# 01-USER_IO.net
KiCad netlist of a schematic drawn in Altium Designer
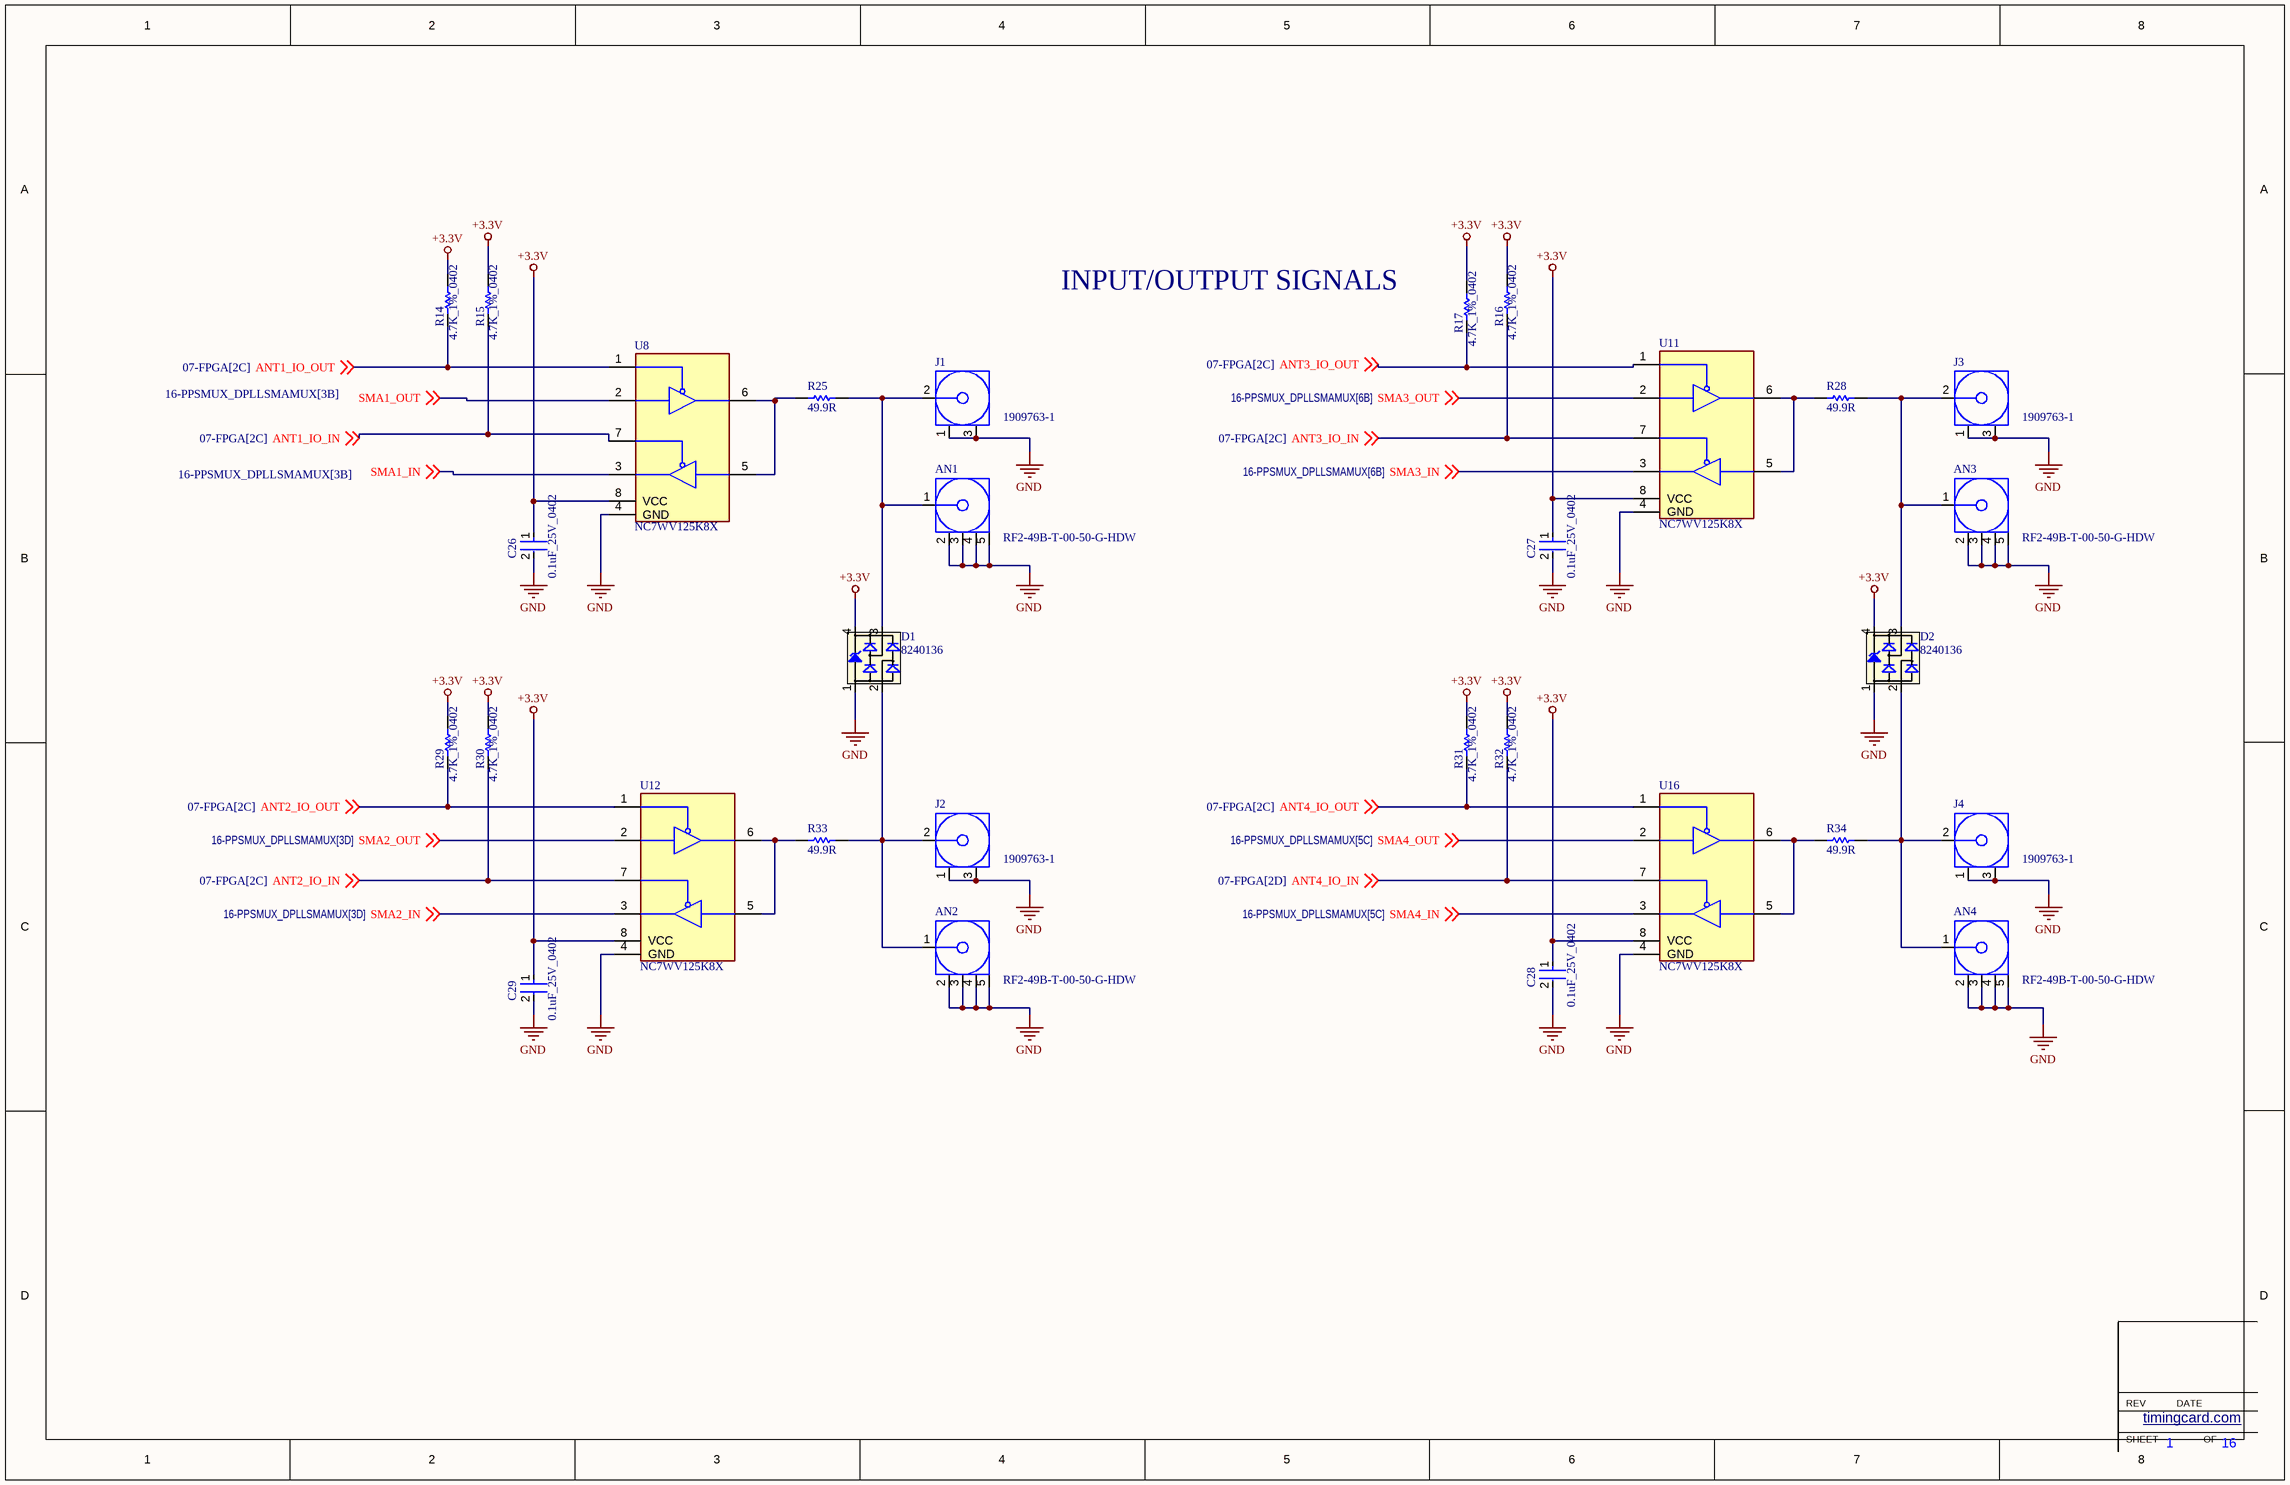
[diagram p0: 01-USER_IO.SchDoc]

(export (version "E")
  (design (tool "Eeschema 10.0.6"))
  (components
    (comp (ref "AN1")
      (value "RF2-49B-T-00-50-G-HDW")
      (footprint "AMPH-901-143-6RFX_V")
      (description "Coaxial connector, 50 Ohm, -65 to 165 degC, 5-Pin THD, RoHS, Bulk")
      (fields (field (name "MANUFACTURER") "Amphenol"))
      (libsource (lib "Altium Content Vault") (part "CN-S-4F-RF5"))
    )
    (comp (ref "AN2")
      (value "RF2-49B-T-00-50-G-HDW")
      (footprint "AMPH-901-143-6RFX_V")
      (description "Coaxial connector, 50 Ohm, -65 to 165 degC, 5-Pin THD, RoHS, Bulk")
      (fields (field (name "MANUFACTURER") "Amphenol"))
      (libsource (lib "Altium Content Vault") (part "CN-S-4F-RF5"))
    )
    (comp (ref "AN3")
      (value "RF2-49B-T-00-50-G-HDW")
      (footprint "AMPH-901-143-6RFX_V")
      (description "Coaxial connector, 50 Ohm, -65 to 165 degC, 5-Pin THD, RoHS, Bulk")
      (fields (field (name "MANUFACTURER") "Amphenol"))
      (libsource (lib "Altium Content Vault") (part "CN-S-4F-RF5"))
    )
    (comp (ref "AN4")
      (value "RF2-49B-T-00-50-G-HDW")
      (footprint "AMPH-901-143-6RFX_V")
      (description "Coaxial connector, 50 Ohm, -65 to 165 degC, 5-Pin THD, RoHS, Bulk")
      (fields (field (name "MANUFACTURER") "Amphenol"))
      (libsource (lib "Altium Content Vault") (part "CN-S-4F-RF5"))
    )
    (comp (ref "C26")
      (value "0.1uF_25V_0402")
      (footprint "FP-0402-L_1_0_1-W_0_5_0_1-IPC_C")
      (description "General Purpose Ceramic Capacitor, 0402, 100nF, 10%, X7R, 15%, 25V")
      (fields (field (name "VOLTAGE") "25V") (field (name "TOLERANCE") "10%"))
      (libsource (lib "Altium Content Vault") (part "b4654b650e69147ec39a6b967a45e02"))
    )
    (comp (ref "C27")
      (value "0.1uF_25V_0402")
      (footprint "FP-0402-L_1_0_1-W_0_5_0_1-IPC_C")
      (description "General Purpose Ceramic Capacitor, 0402, 100nF, 10%, X7R, 15%, 25V")
      (fields (field (name "VOLTAGE") "25V") (field (name "TOLERANCE") "10%"))
      (libsource (lib "Altium Content Vault") (part "b4654b650e69147ec39a6b967a45e02"))
    )
    (comp (ref "C28")
      (value "0.1uF_25V_0402")
      (footprint "FP-0402-L_1_0_1-W_0_5_0_1-IPC_C")
      (description "General Purpose Ceramic Capacitor, 0402, 100nF, 10%, X7R, 15%, 25V")
      (fields (field (name "VOLTAGE") "25V") (field (name "TOLERANCE") "10%"))
      (libsource (lib "Altium Content Vault") (part "b4654b650e69147ec39a6b967a45e02"))
    )
    (comp (ref "C29")
      (value "0.1uF_25V_0402")
      (footprint "FP-0402-L_1_0_1-W_0_5_0_1-IPC_C")
      (description "General Purpose Ceramic Capacitor, 0402, 100nF, 10%, X7R, 15%, 25V")
      (fields (field (name "VOLTAGE") "25V") (field (name "TOLERANCE") "10%"))
      (libsource (lib "Altium Content Vault") (part "b4654b650e69147ec39a6b967a45e02"))
    )
    (comp (ref "D1")
      (value "8240136")
      (footprint "SOT143-4L")
      (description "TVS Diode WE-TVS-HS, VRWM=3.3V")
      (fields (field (name "MANUFACTURER") "Wuerth Elektronik"))
      (libsource (lib "Altium Content Vault") (part "WE-TVS-HS-4"))
    )
    (comp (ref "D2")
      (value "8240136")
      (footprint "SOT143-4L")
      (description "TVS Diode WE-TVS-HS, VRWM=3.3V")
      (fields (field (name "MANUFACTURER") "Wuerth Elektronik"))
      (libsource (lib "Altium Content Vault") (part "WE-TVS-HS-4"))
    )
    (comp (ref "J1")
      (value "1909763-1")
      (footprint "TECO-1909763-1_V")
      (description "Ultra Miniature Coaxial Connector Jack, 60 V, 50 Ohm, -40 to 90 degC, RoHS, Tape and Reel")
      (fields (field (name "MANUFACTURER") "TE Connectivity"))
      (libsource (lib "Altium Content Vault") (part "CN-1P-M-RF3"))
    )
    (comp (ref "J2")
      (value "1909763-1")
      (footprint "TECO-1909763-1_V")
      (description "Ultra Miniature Coaxial Connector Jack, 60 V, 50 Ohm, -40 to 90 degC, RoHS, Tape and Reel")
      (fields (field (name "MANUFACTURER") "TE Connectivity"))
      (libsource (lib "Altium Content Vault") (part "CN-1P-M-RF3"))
    )
    (comp (ref "J3")
      (value "1909763-1")
      (footprint "TECO-1909763-1_V")
      (description "Ultra Miniature Coaxial Connector Jack, 60 V, 50 Ohm, -40 to 90 degC, RoHS, Tape and Reel")
      (fields (field (name "MANUFACTURER") "TE Connectivity"))
      (libsource (lib "Altium Content Vault") (part "CN-1P-M-RF3"))
    )
    (comp (ref "J4")
      (value "1909763-1")
      (footprint "TECO-1909763-1_V")
      (description "Ultra Miniature Coaxial Connector Jack, 60 V, 50 Ohm, -40 to 90 degC, RoHS, Tape and Reel")
      (fields (field (name "MANUFACTURER") "TE Connectivity"))
      (libsource (lib "Altium Content Vault") (part "CN-1P-M-RF3"))
    )
    (comp (ref "R14")
      (value "4.7K_1%_0402")
      (footprint "RESC1005X40X25NL10T10")
      (fields (field (name "MANUFACTURER") "Bourns") (field (name "PART NUMBER") "CR0402-FX-4701GLF"))
      (libsource (lib "Altium Content Vault") (part "RES"))
    )
    (comp (ref "R15")
      (value "4.7K_1%_0402")
      (footprint "RESC1005X40X25NL10T10")
      (fields (field (name "MANUFACTURER") "Bourns") (field (name "PART NUMBER") "CR0402-FX-4701GLF"))
      (libsource (lib "Altium Content Vault") (part "RES"))
    )
    (comp (ref "R16")
      (value "4.7K_1%_0402")
      (footprint "RESC1005X40X25NL10T10")
      (fields (field (name "MANUFACTURER") "Bourns") (field (name "PART NUMBER") "CR0402-FX-4701GLF"))
      (libsource (lib "Altium Content Vault") (part "RES"))
    )
    (comp (ref "R17")
      (value "4.7K_1%_0402")
      (footprint "RESC1005X40X25NL10T10")
      (fields (field (name "MANUFACTURER") "Bourns") (field (name "PART NUMBER") "CR0402-FX-4701GLF"))
      (libsource (lib "Altium Content Vault") (part "RES"))
    )
    (comp (ref "R25")
      (value "49.9R")
      (footprint "RESC1608X55X25NL10T15")
      (libsource (lib "Altium Content Vault") (part "RES-2"))
    )
    (comp (ref "R28")
      (value "49.9R")
      (footprint "RESC1608X55X25NL10T15")
      (libsource (lib "Altium Content Vault") (part "RES-2"))
    )
    (comp (ref "R29")
      (value "4.7K_1%_0402")
      (footprint "RESC1005X40X25NL10T10")
      (fields (field (name "MANUFACTURER") "Bourns") (field (name "PART NUMBER") "CR0402-FX-4701GLF"))
      (libsource (lib "Altium Content Vault") (part "RES"))
    )
    (comp (ref "R30")
      (value "4.7K_1%_0402")
      (footprint "RESC1005X40X25NL10T10")
      (fields (field (name "MANUFACTURER") "Bourns") (field (name "PART NUMBER") "CR0402-FX-4701GLF"))
      (libsource (lib "Altium Content Vault") (part "RES"))
    )
    (comp (ref "R31")
      (value "4.7K_1%_0402")
      (footprint "RESC1005X40X25NL10T10")
      (fields (field (name "MANUFACTURER") "Bourns") (field (name "PART NUMBER") "CR0402-FX-4701GLF"))
      (libsource (lib "Altium Content Vault") (part "RES"))
    )
    (comp (ref "R32")
      (value "4.7K_1%_0402")
      (footprint "RESC1005X40X25NL10T10")
      (fields (field (name "MANUFACTURER") "Bourns") (field (name "PART NUMBER") "CR0402-FX-4701GLF"))
      (libsource (lib "Altium Content Vault") (part "RES"))
    )
    (comp (ref "R33")
      (value "49.9R")
      (footprint "RESC1608X55X25NL10T15")
      (libsource (lib "Altium Content Vault") (part "RES-2"))
    )
    (comp (ref "R34")
      (value "49.9R")
      (footprint "RESC1608X55X25NL10T15")
      (libsource (lib "Altium Content Vault") (part "RES-2"))
    )
    (comp (ref "U8")
      (value "NC7WV125K8X")
      (footprint "SamacSys:SOP50P310X90-8N")
      (description "Integrated Circuit")
      (fields (field (name "MOUSER PART NUMBER") "512-NC7WV125K8X"))
      (libsource (lib "SamacSys") (part "NC7WV125K8X"))
    )
    (comp (ref "U11")
      (value "NC7WV125K8X")
      (footprint "SamacSys:SOP50P310X90-8N")
      (description "Integrated Circuit")
      (fields (field (name "MOUSER PART NUMBER") "512-NC7WV125K8X"))
      (libsource (lib "SamacSys") (part "NC7WV125K8X"))
    )
    (comp (ref "U12")
      (value "NC7WV125K8X")
      (footprint "SamacSys:SOP50P310X90-8N")
      (description "Integrated Circuit")
      (fields (field (name "MOUSER PART NUMBER") "512-NC7WV125K8X"))
      (libsource (lib "SamacSys") (part "NC7WV125K8X"))
    )
    (comp (ref "U16")
      (value "NC7WV125K8X")
      (footprint "SamacSys:SOP50P310X90-8N")
      (description "Integrated Circuit")
      (fields (field (name "MOUSER PART NUMBER") "512-NC7WV125K8X"))
      (libsource (lib "SamacSys") (part "NC7WV125K8X"))
    )
  )
  (nets
    (net (code "1") (name "+3.3V") (class "Default")
      (node (ref "C26") (pin "1") (pinfunction "1_1") (pintype "passive"))
      (node (ref "C27") (pin "1") (pinfunction "1_1") (pintype "passive"))
      (node (ref "C28") (pin "1") (pinfunction "1_1") (pintype "passive"))
      (node (ref "C29") (pin "1") (pinfunction "1_1") (pintype "passive"))
      (node (ref "D1") (pin "4") (pinfunction "VDD_4") (pintype "passive"))
      (node (ref "D2") (pin "4") (pinfunction "VDD_4") (pintype "passive"))
      (node (ref "R14") (pin "1") (pinfunction "1_1") (pintype "passive"))
      (node (ref "R15") (pin "1") (pinfunction "1_1") (pintype "passive"))
      (node (ref "R16") (pin "1") (pinfunction "1_1") (pintype "passive"))
      (node (ref "R17") (pin "1") (pinfunction "1_1") (pintype "passive"))
      (node (ref "R29") (pin "1") (pinfunction "1_1") (pintype "passive"))
      (node (ref "R30") (pin "1") (pinfunction "1_1") (pintype "passive"))
      (node (ref "R31") (pin "1") (pinfunction "1_1") (pintype "passive"))
      (node (ref "R32") (pin "1") (pinfunction "1_1") (pintype "passive"))
      (node (ref "U11") (pin "8") (pinfunction "VCC_8") (pintype "passive"))
      (node (ref "U12") (pin "8") (pinfunction "VCC_8") (pintype "passive"))
      (node (ref "U16") (pin "8") (pinfunction "VCC_8") (pintype "passive"))
      (node (ref "U8") (pin "8") (pinfunction "VCC_8") (pintype "passive"))
    )
    (net (code "2") (name "ANT1_IO_IN") (class "Default")
      (node (ref "R15") (pin "2") (pinfunction "2_2") (pintype "passive"))
      (node (ref "U8") (pin "7") (pintype "passive"))
    )
    (net (code "3") (name "ANT1_IO_OUT") (class "Default")
      (node (ref "R14") (pin "2") (pinfunction "2_2") (pintype "passive"))
      (node (ref "U8") (pin "1") (pintype "passive"))
    )
    (net (code "4") (name "ANT2_IO_IN") (class "Default")
      (node (ref "R30") (pin "2") (pinfunction "2_2") (pintype "passive"))
      (node (ref "U12") (pin "7") (pintype "passive"))
    )
    (net (code "5") (name "ANT2_IO_OUT") (class "Default")
      (node (ref "R29") (pin "2") (pinfunction "2_2") (pintype "passive"))
      (node (ref "U12") (pin "1") (pintype "passive"))
    )
    (net (code "6") (name "ANT3_IO_IN") (class "Default")
      (node (ref "R16") (pin "2") (pinfunction "2_2") (pintype "passive"))
      (node (ref "U11") (pin "7") (pintype "passive"))
    )
    (net (code "7") (name "ANT3_IO_OUT") (class "Default")
      (node (ref "R17") (pin "2") (pinfunction "2_2") (pintype "passive"))
      (node (ref "U11") (pin "1") (pintype "passive"))
    )
    (net (code "8") (name "ANT4_IO_IN") (class "Default")
      (node (ref "R32") (pin "2") (pinfunction "2_2") (pintype "passive"))
      (node (ref "U16") (pin "7") (pintype "passive"))
    )
    (net (code "9") (name "ANT4_IO_OUT") (class "Default")
      (node (ref "R31") (pin "2") (pinfunction "2_2") (pintype "passive"))
      (node (ref "U16") (pin "1") (pintype "passive"))
    )
    (net (code "10") (name "GND") (class "Default")
      (node (ref "AN1") (pin "2") (pinfunction "2_2") (pintype "passive"))
      (node (ref "AN1") (pin "3") (pinfunction "3_3") (pintype "passive"))
      (node (ref "AN1") (pin "4") (pinfunction "4_4") (pintype "passive"))
      (node (ref "AN1") (pin "5") (pinfunction "5_5") (pintype "passive"))
      (node (ref "AN2") (pin "2") (pinfunction "2_2") (pintype "passive"))
      (node (ref "AN2") (pin "3") (pinfunction "3_3") (pintype "passive"))
      (node (ref "AN2") (pin "4") (pinfunction "4_4") (pintype "passive"))
      (node (ref "AN2") (pin "5") (pinfunction "5_5") (pintype "passive"))
      (node (ref "AN3") (pin "2") (pinfunction "2_2") (pintype "passive"))
      (node (ref "AN3") (pin "3") (pinfunction "3_3") (pintype "passive"))
      (node (ref "AN3") (pin "4") (pinfunction "4_4") (pintype "passive"))
      (node (ref "AN3") (pin "5") (pinfunction "5_5") (pintype "passive"))
      (node (ref "AN4") (pin "2") (pinfunction "2_2") (pintype "passive"))
      (node (ref "AN4") (pin "3") (pinfunction "3_3") (pintype "passive"))
      (node (ref "AN4") (pin "4") (pinfunction "4_4") (pintype "passive"))
      (node (ref "AN4") (pin "5") (pinfunction "5_5") (pintype "passive"))
      (node (ref "C26") (pin "2") (pinfunction "2_2") (pintype "passive"))
      (node (ref "C27") (pin "2") (pinfunction "2_2") (pintype "passive"))
      (node (ref "C28") (pin "2") (pinfunction "2_2") (pintype "passive"))
      (node (ref "C29") (pin "2") (pinfunction "2_2") (pintype "passive"))
      (node (ref "D1") (pin "1") (pinfunction "GND_1") (pintype "passive"))
      (node (ref "D2") (pin "1") (pinfunction "GND_1") (pintype "passive"))
      (node (ref "J1") (pin "1") (pinfunction "1_1") (pintype "passive"))
      (node (ref "J1") (pin "3") (pinfunction "3_3") (pintype "passive"))
      (node (ref "J2") (pin "1") (pinfunction "1_1") (pintype "passive"))
      (node (ref "J2") (pin "3") (pinfunction "3_3") (pintype "passive"))
      (node (ref "J3") (pin "1") (pinfunction "1_1") (pintype "passive"))
      (node (ref "J3") (pin "3") (pinfunction "3_3") (pintype "passive"))
      (node (ref "J4") (pin "1") (pinfunction "1_1") (pintype "passive"))
      (node (ref "J4") (pin "3") (pinfunction "3_3") (pintype "passive"))
      (node (ref "U11") (pin "4") (pinfunction "GND_4") (pintype "passive"))
      (node (ref "U12") (pin "4") (pinfunction "GND_4") (pintype "passive"))
      (node (ref "U16") (pin "4") (pinfunction "GND_4") (pintype "passive"))
      (node (ref "U8") (pin "4") (pinfunction "GND_4") (pintype "passive"))
    )
    (net (code "11") (name "Net-(D1-I{slash}O1)") (class "Default")
      (node (ref "AN2") (pin "1") (pinfunction "1_1") (pintype "passive"))
      (node (ref "D1") (pin "2") (pinfunction "I/O1_2") (pintype "passive"))
      (node (ref "J2") (pin "2") (pinfunction "2_2") (pintype "passive"))
      (node (ref "R33") (pin "2") (pinfunction "2_2") (pintype "passive"))
    )
    (net (code "12") (name "Net-(D1-I{slash}O2)") (class "Default")
      (node (ref "AN1") (pin "1") (pinfunction "1_1") (pintype "passive"))
      (node (ref "D1") (pin "3") (pinfunction "I/O2_3") (pintype "passive"))
      (node (ref "J1") (pin "2") (pinfunction "2_2") (pintype "passive"))
      (node (ref "R25") (pin "2") (pinfunction "2_2") (pintype "passive"))
    )
    (net (code "13") (name "Net-(D2-I{slash}O1)") (class "Default")
      (node (ref "AN4") (pin "1") (pinfunction "1_1") (pintype "passive"))
      (node (ref "D2") (pin "2") (pinfunction "I/O1_2") (pintype "passive"))
      (node (ref "J4") (pin "2") (pinfunction "2_2") (pintype "passive"))
      (node (ref "R34") (pin "2") (pinfunction "2_2") (pintype "passive"))
    )
    (net (code "14") (name "Net-(D2-I{slash}O2)") (class "Default")
      (node (ref "AN3") (pin "1") (pinfunction "1_1") (pintype "passive"))
      (node (ref "D2") (pin "3") (pinfunction "I/O2_3") (pintype "passive"))
      (node (ref "J3") (pin "2") (pinfunction "2_2") (pintype "passive"))
      (node (ref "R28") (pin "2") (pinfunction "2_2") (pintype "passive"))
    )
    (net (code "15") (name "Net-(R25-Pad1)") (class "Default")
      (node (ref "R25") (pin "1") (pinfunction "1_1") (pintype "passive"))
      (node (ref "U8") (pin "5") (pintype "passive"))
      (node (ref "U8") (pin "6") (pintype "passive"))
    )
    (net (code "16") (name "Net-(R28-Pad1)") (class "Default")
      (node (ref "R28") (pin "1") (pinfunction "1_1") (pintype "passive"))
      (node (ref "U11") (pin "5") (pintype "passive"))
      (node (ref "U11") (pin "6") (pintype "passive"))
    )
    (net (code "17") (name "Net-(R33-Pad1)") (class "Default")
      (node (ref "R33") (pin "1") (pinfunction "1_1") (pintype "passive"))
      (node (ref "U12") (pin "5") (pintype "passive"))
      (node (ref "U12") (pin "6") (pintype "passive"))
    )
    (net (code "18") (name "Net-(R34-Pad1)") (class "Default")
      (node (ref "R34") (pin "1") (pinfunction "1_1") (pintype "passive"))
      (node (ref "U16") (pin "5") (pintype "passive"))
      (node (ref "U16") (pin "6") (pintype "passive"))
    )
    (net (code "19") (name "SMA1_IN") (class "Default") (node (ref "U8") (pin "3") (pintype "passive")))
    (net (code "20") (name "SMA1_OUT") (class "Default") (node (ref "U8") (pin "2") (pintype "passive")))
    (net (code "21") (name "SMA2_IN") (class "Default") (node (ref "U12") (pin "3") (pintype "passive")))
    (net (code "22") (name "SMA2_OUT") (class "Default") (node (ref "U12") (pin "2") (pintype "passive")))
    (net (code "23") (name "SMA3_IN") (class "Default") (node (ref "U11") (pin "3") (pintype "passive")))
    (net (code "24") (name "SMA3_OUT") (class "Default") (node (ref "U11") (pin "2") (pintype "passive")))
    (net (code "25") (name "SMA4_IN") (class "Default") (node (ref "U16") (pin "3") (pintype "passive")))
    (net (code "26") (name "SMA4_OUT") (class "Default") (node (ref "U16") (pin "2") (pintype "passive")))
  )
)
